# HEATER.net
KiCad netlist of a schematic drawn in Altium Designer
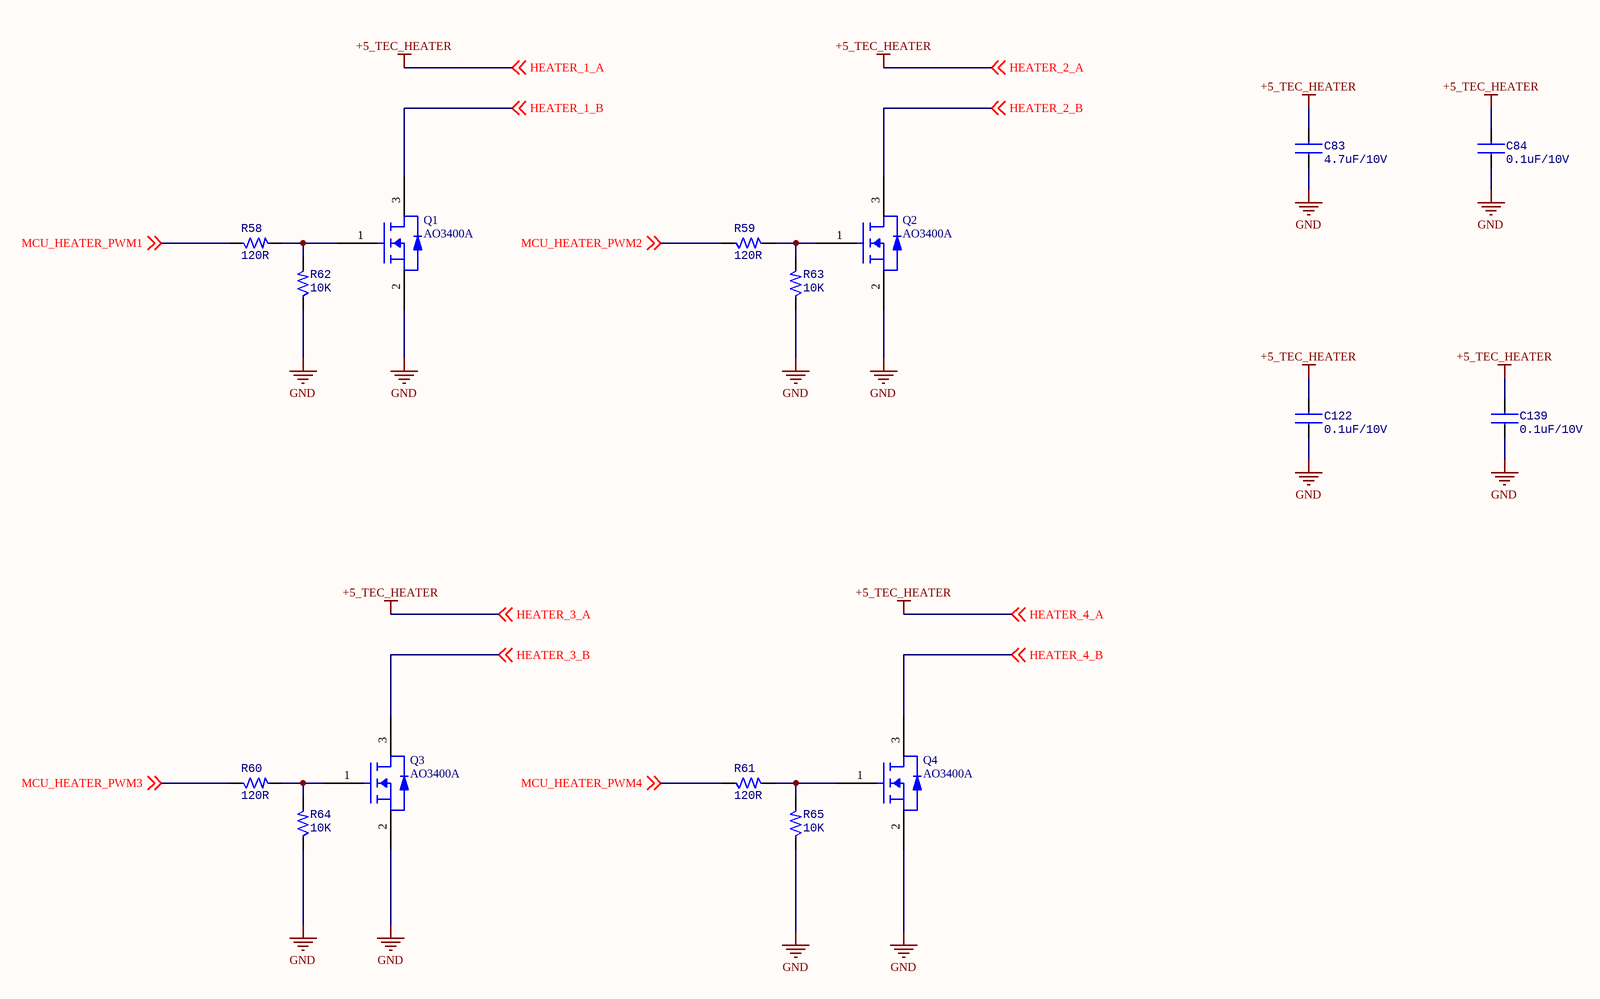
[diagram p0: HEATER.SchDoc]

(export (version "E")
  (design (tool "Eeschema 10.0.6"))
  (components
    (comp (ref "C83") (value "4.7uF/10V") (footprint "CAP-CER-0603") (libsource (lib "ID") (part "CAP-CER")))
    (comp (ref "C84") (value "0.1uF/10V") (footprint "CAP-CER-0603") (libsource (lib "ID") (part "CAP-CER")))
    (comp (ref "C122") (value "0.1uF/10V") (footprint "CAP-CER-0603") (libsource (lib "ID") (part "CAP-CER")))
    (comp (ref "C139") (value "0.1uF/10V") (footprint "CAP-CER-0603") (libsource (lib "ID") (part "CAP-CER")))
    (comp (ref "Q1")
      (value "AO3400A")
      (footprint "SOT-23")
      (description "MOSFET N-Channel Vds=60V Id=300mA with ESD Protection")
      (fields
        (field (name "MANUFACTURER") "Nexperia")
        (field (name "MANUFACTURER PART NUMBER") "2N7002NXAKR")
      )
      (libsource (lib "Schematic-Lib-PhilsLab") (part "2N7002NXAKR"))
    )
    (comp (ref "Q2")
      (value "AO3400A")
      (footprint "SOT-23")
      (description "MOSFET N-Channel Vds=60V Id=300mA with ESD Protection")
      (fields
        (field (name "MANUFACTURER") "Nexperia")
        (field (name "MANUFACTURER PART NUMBER") "2N7002NXAKR")
      )
      (libsource (lib "Schematic-Lib-PhilsLab") (part "2N7002NXAKR"))
    )
    (comp (ref "Q3")
      (value "AO3400A")
      (footprint "SOT-23")
      (description "MOSFET N-Channel Vds=60V Id=300mA with ESD Protection")
      (fields
        (field (name "MANUFACTURER") "Nexperia")
        (field (name "MANUFACTURER PART NUMBER") "2N7002NXAKR")
      )
      (libsource (lib "Schematic-Lib-PhilsLab") (part "2N7002NXAKR"))
    )
    (comp (ref "Q4")
      (value "AO3400A")
      (footprint "SOT-23")
      (description "MOSFET N-Channel Vds=60V Id=300mA with ESD Protection")
      (fields
        (field (name "MANUFACTURER") "Nexperia")
        (field (name "MANUFACTURER PART NUMBER") "2N7002NXAKR")
      )
      (libsource (lib "Schematic-Lib-PhilsLab") (part "2N7002NXAKR"))
    )
    (comp (ref "R58") (value "120R") (footprint "RES-SMD-0603") (libsource (lib "ID") (part "RES-SMD")))
    (comp (ref "R59") (value "120R") (footprint "RES-SMD-0603") (libsource (lib "ID") (part "RES-SMD")))
    (comp (ref "R60") (value "120R") (footprint "RES-SMD-0603") (libsource (lib "ID") (part "RES-SMD")))
    (comp (ref "R61") (value "120R") (footprint "RES-SMD-0603") (libsource (lib "ID") (part "RES-SMD")))
    (comp (ref "R62") (value "10K") (footprint "RES-SMD-0603") (libsource (lib "ID") (part "RES-SMD")))
    (comp (ref "R63") (value "10K") (footprint "RES-SMD-0603") (libsource (lib "ID") (part "RES-SMD")))
    (comp (ref "R64") (value "10K") (footprint "RES-SMD-0603") (libsource (lib "ID") (part "RES-SMD")))
    (comp (ref "R65") (value "10K") (footprint "RES-SMD-0603") (libsource (lib "ID") (part "RES-SMD")))
  )
  (nets
    (net (code "1") (name "+5_TEC_HEATER") (class "Default")
      (node (ref "C122") (pin "1") (pinfunction "1_1") (pintype "passive"))
      (node (ref "C139") (pin "1") (pinfunction "1_1") (pintype "passive"))
      (node (ref "C83") (pin "1") (pinfunction "1_1") (pintype "passive"))
      (node (ref "C84") (pin "1") (pinfunction "1_1") (pintype "passive"))
    )
    (net (code "2") (name "GND") (class "Default")
      (node (ref "C122") (pin "2") (pinfunction "2_2") (pintype "passive"))
      (node (ref "C139") (pin "2") (pinfunction "2_2") (pintype "passive"))
      (node (ref "C83") (pin "2") (pinfunction "2_2") (pintype "passive"))
      (node (ref "C84") (pin "2") (pinfunction "2_2") (pintype "passive"))
      (node (ref "Q1") (pin "2") (pinfunction "306_2") (pintype "passive"))
      (node (ref "Q2") (pin "2") (pinfunction "306_2") (pintype "passive"))
      (node (ref "Q3") (pin "2") (pinfunction "306_2") (pintype "passive"))
      (node (ref "Q4") (pin "2") (pinfunction "306_2") (pintype "passive"))
      (node (ref "R62") (pin "1") (pinfunction "1_1") (pintype "passive"))
      (node (ref "R63") (pin "1") (pinfunction "1_1") (pintype "passive"))
      (node (ref "R64") (pin "1") (pinfunction "1_1") (pintype "passive"))
      (node (ref "R65") (pin "1") (pinfunction "1_1") (pintype "passive"))
    )
    (net (code "3") (name "HEATER_1_B") (class "Default")
      (node (ref "Q1") (pin "3") (pinfunction "1_3") (pintype "passive"))
    )
    (net (code "4") (name "HEATER_2_B") (class "Default")
      (node (ref "Q2") (pin "3") (pinfunction "1_3") (pintype "passive"))
    )
    (net (code "5") (name "HEATER_3_B") (class "Default")
      (node (ref "Q3") (pin "3") (pinfunction "1_3") (pintype "passive"))
    )
    (net (code "6") (name "HEATER_4_B") (class "Default")
      (node (ref "Q4") (pin "3") (pinfunction "1_3") (pintype "passive"))
    )
    (net (code "7") (name "MCU_HEATER_PWM1") (class "Default")
      (node (ref "R58") (pin "1") (pinfunction "1_1") (pintype "passive"))
    )
    (net (code "8") (name "MCU_HEATER_PWM2") (class "Default")
      (node (ref "R59") (pin "1") (pinfunction "1_1") (pintype "passive"))
    )
    (net (code "9") (name "MCU_HEATER_PWM3") (class "Default")
      (node (ref "R60") (pin "1") (pinfunction "1_1") (pintype "passive"))
    )
    (net (code "10") (name "MCU_HEATER_PWM4") (class "Default")
      (node (ref "R61") (pin "1") (pinfunction "1_1") (pintype "passive"))
    )
    (net (code "11") (name "Net-(Q1-2)") (class "Default")
      (node (ref "Q1") (pin "1") (pinfunction "2_1") (pintype "passive"))
      (node (ref "R58") (pin "2") (pinfunction "2_2") (pintype "passive"))
      (node (ref "R62") (pin "2") (pinfunction "2_2") (pintype "passive"))
    )
    (net (code "12") (name "Net-(Q2-2)") (class "Default")
      (node (ref "Q2") (pin "1") (pinfunction "2_1") (pintype "passive"))
      (node (ref "R59") (pin "2") (pinfunction "2_2") (pintype "passive"))
      (node (ref "R63") (pin "2") (pinfunction "2_2") (pintype "passive"))
    )
    (net (code "13") (name "Net-(Q3-2)") (class "Default")
      (node (ref "Q3") (pin "1") (pinfunction "2_1") (pintype "passive"))
      (node (ref "R60") (pin "2") (pinfunction "2_2") (pintype "passive"))
      (node (ref "R64") (pin "2") (pinfunction "2_2") (pintype "passive"))
    )
    (net (code "14") (name "Net-(Q4-2)") (class "Default")
      (node (ref "Q4") (pin "1") (pinfunction "2_1") (pintype "passive"))
      (node (ref "R61") (pin "2") (pinfunction "2_2") (pintype "passive"))
      (node (ref "R65") (pin "2") (pinfunction "2_2") (pintype "passive"))
    )
  )
)
